# PicoMiteUSB.net
KiCad netlist of a schematic drawn in EasyEDA Pro
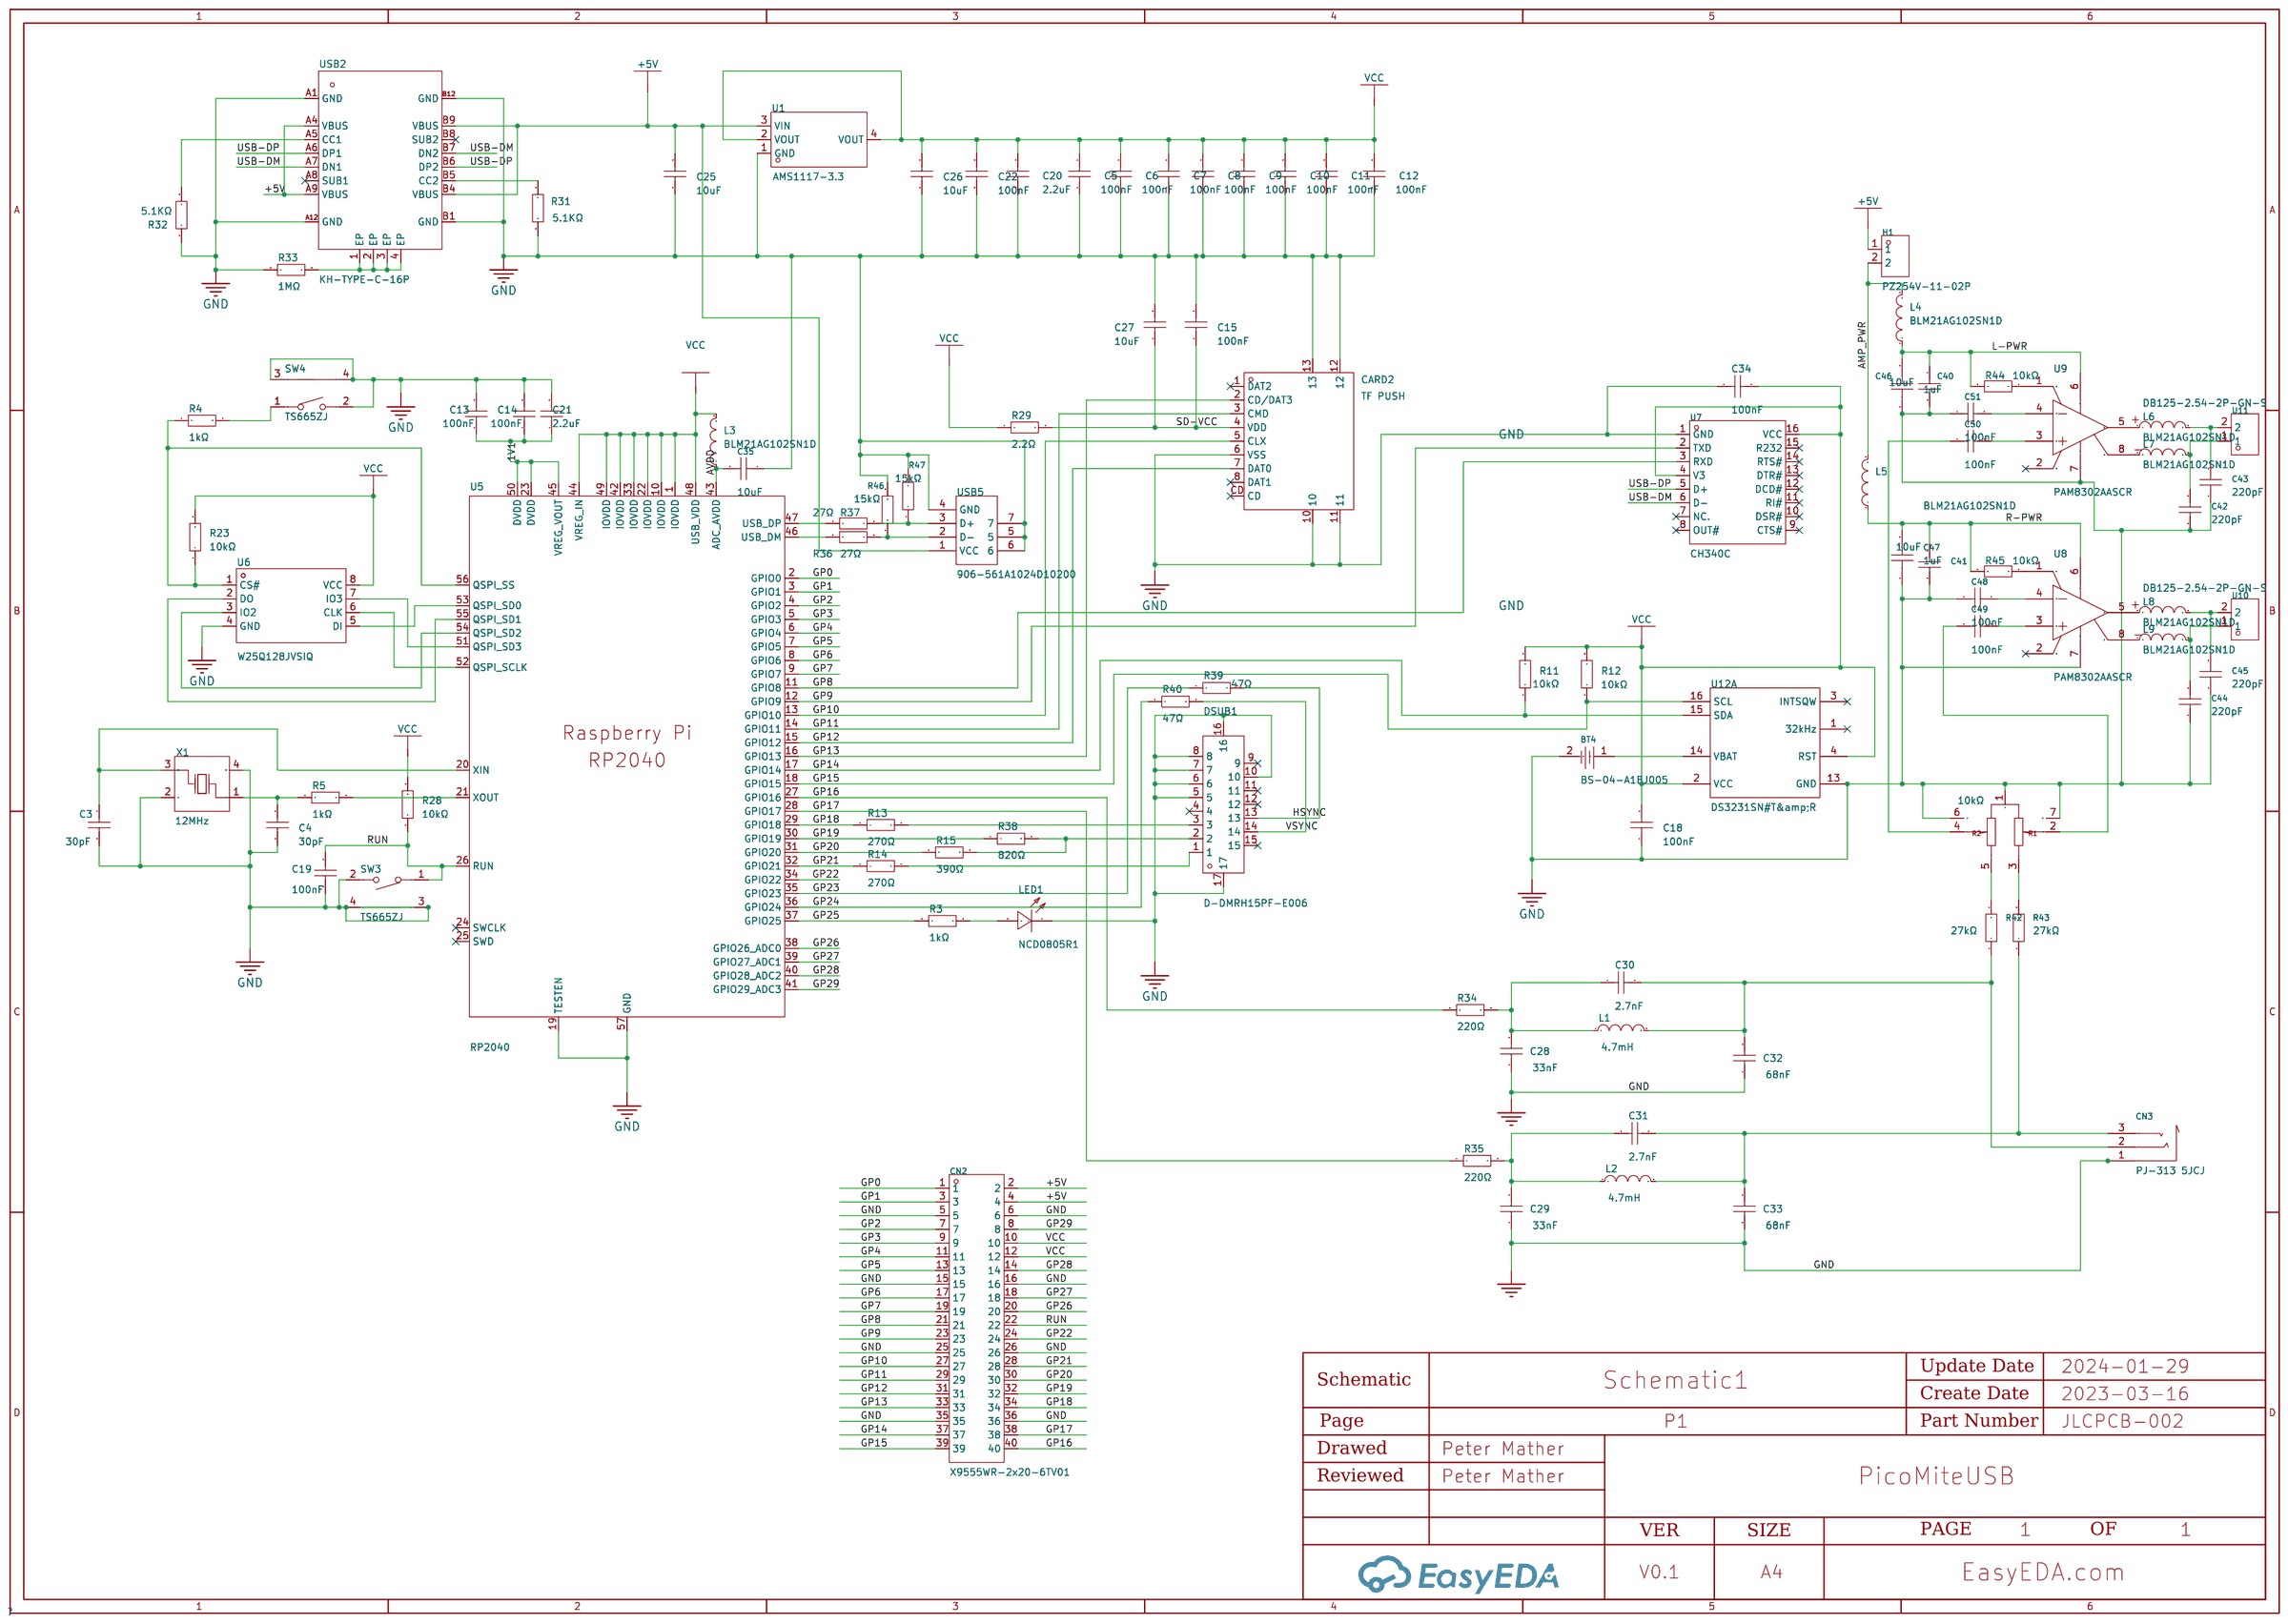
[diagram p0: schematic sheet]

(export (version "E")
  (design (tool "Eeschema 10.0.6"))
  (components
    (comp (ref "BT4")
      (value "BS-04-A1BJ005")
      (footprint "easyedapro:BAT-TH_BS-04-A1BJ004")
      (fields (field (name "Manufacturer") "MYOUNG(美阳)"))
      (libsource (lib "easyedapro") (part "BS-04-A1BJ005"))
    )
    (comp (ref "C3")
      (value "30pF")
      (footprint "easyedapro:C0805")
      (fields (field (name "Manufacturer Part") "0402CG300J500NT") (field (name "Manufacturer") "FH(风华)"))
      (libsource (lib "easyedapro") (part "CC0805JRNPO9BN300"))
    )
    (comp (ref "C4")
      (value "30pF")
      (footprint "easyedapro:C0805")
      (fields (field (name "Manufacturer Part") "0402CG300J500NT") (field (name "Manufacturer") "FH(风华)"))
      (libsource (lib "easyedapro") (part "CC0805JRNPO9BN300"))
    )
    (comp (ref "C5")
      (value "100nF")
      (footprint "easyedapro:C0603")
      (fields
        (field (name "Manufacturer Part") "CL05B104KO5NNNC")
        (field (name "Manufacturer") "SAMSUNG(三星)")
      )
      (libsource (lib "easyedapro") (part "CL10A225KO8NNNC"))
    )
    (comp (ref "C6")
      (value "100nF")
      (footprint "easyedapro:C0603")
      (fields
        (field (name "Manufacturer Part") "CL05B104KO5NNNC")
        (field (name "Manufacturer") "SAMSUNG(三星)")
      )
      (libsource (lib "easyedapro") (part "CL10A225KO8NNNC"))
    )
    (comp (ref "C7")
      (value "100nF")
      (footprint "easyedapro:C0603")
      (fields
        (field (name "Manufacturer Part") "CL05B104KO5NNNC")
        (field (name "Manufacturer") "SAMSUNG(三星)")
      )
      (libsource (lib "easyedapro") (part "CL10A225KO8NNNC"))
    )
    (comp (ref "C8")
      (value "100nF")
      (footprint "easyedapro:C0603")
      (fields
        (field (name "Manufacturer Part") "CL05B104KO5NNNC")
        (field (name "Manufacturer") "SAMSUNG(三星)")
      )
      (libsource (lib "easyedapro") (part "CL10A225KO8NNNC"))
    )
    (comp (ref "C9")
      (value "100nF")
      (footprint "easyedapro:C0603")
      (fields
        (field (name "Manufacturer Part") "CL05B104KO5NNNC")
        (field (name "Manufacturer") "SAMSUNG(三星)")
      )
      (libsource (lib "easyedapro") (part "CL10A225KO8NNNC"))
    )
    (comp (ref "C10")
      (value "100nF")
      (footprint "easyedapro:C0603")
      (fields
        (field (name "Manufacturer Part") "CL05B104KO5NNNC")
        (field (name "Manufacturer") "SAMSUNG(三星)")
      )
      (libsource (lib "easyedapro") (part "CL10A225KO8NNNC"))
    )
    (comp (ref "C11")
      (value "100nF")
      (footprint "easyedapro:C0603")
      (fields
        (field (name "Manufacturer Part") "CL05B104KO5NNNC")
        (field (name "Manufacturer") "SAMSUNG(三星)")
      )
      (libsource (lib "easyedapro") (part "CL10A225KO8NNNC"))
    )
    (comp (ref "C12")
      (value "100nF")
      (footprint "easyedapro:C0603")
      (fields
        (field (name "Manufacturer Part") "CL05B104KO5NNNC")
        (field (name "Manufacturer") "SAMSUNG(三星)")
      )
      (libsource (lib "easyedapro") (part "CL10A225KO8NNNC"))
    )
    (comp (ref "C13")
      (value "100nF")
      (footprint "easyedapro:C0603")
      (fields
        (field (name "Manufacturer Part") "CL05B104KO5NNNC")
        (field (name "Manufacturer") "SAMSUNG(三星)")
      )
      (libsource (lib "easyedapro") (part "CL10A225KO8NNNC"))
    )
    (comp (ref "C14")
      (value "100nF")
      (footprint "easyedapro:C0603")
      (fields
        (field (name "Manufacturer Part") "CL05B104KO5NNNC")
        (field (name "Manufacturer") "SAMSUNG(三星)")
      )
      (libsource (lib "easyedapro") (part "CL10A225KO8NNNC"))
    )
    (comp (ref "C15")
      (value "100nF")
      (footprint "easyedapro:C0603")
      (fields
        (field (name "Manufacturer Part") "CL05B104KO5NNNC")
        (field (name "Manufacturer") "SAMSUNG(三星)")
      )
      (libsource (lib "easyedapro") (part "CL10A225KO8NNNC"))
    )
    (comp (ref "C18")
      (value "100nF")
      (footprint "easyedapro:C0603")
      (fields
        (field (name "Manufacturer Part") "CL05B104KO5NNNC")
        (field (name "Manufacturer") "SAMSUNG(三星)")
      )
      (libsource (lib "easyedapro") (part "CL10A225KO8NNNC"))
    )
    (comp (ref "C19")
      (value "100nF")
      (footprint "easyedapro:C0603")
      (fields
        (field (name "Manufacturer Part") "CL05B104KO5NNNC")
        (field (name "Manufacturer") "SAMSUNG(三星)")
      )
      (libsource (lib "easyedapro") (part "CL10A225KO8NNNC"))
    )
    (comp (ref "C20")
      (value "2.2uF")
      (footprint "easyedapro:C0402_NEW")
      (fields
        (field (name "Manufacturer Part") "CL10A225KO8NNNC")
        (field (name "Manufacturer") "SAMSUNG(三星)")
      )
      (libsource (lib "easyedapro") (part "CL05B104KO5NNNC"))
    )
    (comp (ref "C21")
      (value "2.2uF")
      (footprint "easyedapro:C0402_NEW")
      (fields
        (field (name "Manufacturer Part") "CL10A225KO8NNNC")
        (field (name "Manufacturer") "SAMSUNG(三星)")
      )
      (libsource (lib "easyedapro") (part "CL05B104KO5NNNC"))
    )
    (comp (ref "C22")
      (value "100nF")
      (footprint "easyedapro:C0603")
      (fields
        (field (name "Manufacturer Part") "CL05B104KO5NNNC")
        (field (name "Manufacturer") "SAMSUNG(三星)")
      )
      (libsource (lib "easyedapro") (part "CL10A225KO8NNNC"))
    )
    (comp (ref "C25")
      (value "10uF")
      (footprint "easyedapro:C1206")
      (fields
        (field (name "Manufacturer Part") "CL31A106KBHNNNE")
        (field (name "Manufacturer") "SAMSUNG(三星)")
      )
      (libsource (lib "easyedapro") (part "CL31A106KBHNNNE"))
    )
    (comp (ref "C26")
      (value "10uF")
      (footprint "easyedapro:C1206")
      (fields
        (field (name "Manufacturer Part") "CL31A106KBHNNNE")
        (field (name "Manufacturer") "SAMSUNG(三星)")
      )
      (libsource (lib "easyedapro") (part "CL31A106KBHNNNE"))
    )
    (comp (ref "C27")
      (value "10uF")
      (footprint "easyedapro:C1206")
      (fields
        (field (name "Manufacturer Part") "CL31A106KBHNNNE")
        (field (name "Manufacturer") "SAMSUNG(三星)")
      )
      (libsource (lib "easyedapro") (part "CL31A106KBHNNNE"))
    )
    (comp (ref "C28")
      (value "33nF")
      (footprint "easyedapro:C0603")
      (fields
        (field (name "Manufacturer Part") "CL10B333KB8NNNC")
        (field (name "Manufacturer") "SAMSUNG(三星)")
      )
      (libsource (lib "easyedapro") (part "CL10B333KB8NNNC"))
    )
    (comp (ref "C29")
      (value "33nF")
      (footprint "easyedapro:C0603")
      (fields
        (field (name "Manufacturer Part") "CL10B333KB8NNNC")
        (field (name "Manufacturer") "SAMSUNG(三星)")
      )
      (libsource (lib "easyedapro") (part "CL10B333KB8NNNC"))
    )
    (comp (ref "C30")
      (value "2.7nF")
      (footprint "easyedapro:C0603")
      (fields (field (name "Manufacturer Part") "0603B272K500NT") (field (name "Manufacturer") "FH(风华)"))
      (libsource (lib "easyedapro") (part "0603B272K500NT"))
    )
    (comp (ref "C31")
      (value "2.7nF")
      (footprint "easyedapro:C0603")
      (fields (field (name "Manufacturer Part") "0603B272K500NT") (field (name "Manufacturer") "FH(风华)"))
      (libsource (lib "easyedapro") (part "0603B272K500NT"))
    )
    (comp (ref "C32")
      (value "68nF")
      (footprint "easyedapro:C0603")
      (fields
        (field (name "Manufacturer Part") "CL10B683KB8NNNC")
        (field (name "Manufacturer") "SAMSUNG(三星)")
      )
      (libsource (lib "easyedapro") (part "CL10B683KB8NNNC"))
    )
    (comp (ref "C33")
      (value "68nF")
      (footprint "easyedapro:C0603")
      (fields
        (field (name "Manufacturer Part") "CL10B683KB8NNNC")
        (field (name "Manufacturer") "SAMSUNG(三星)")
      )
      (libsource (lib "easyedapro") (part "CL10B683KB8NNNC"))
    )
    (comp (ref "C34")
      (value "100nF")
      (footprint "easyedapro:C0603")
      (fields
        (field (name "Manufacturer Part") "CL05B104KO5NNNC")
        (field (name "Manufacturer") "SAMSUNG(三星)")
      )
      (libsource (lib "easyedapro") (part "CL10A225KO8NNNC"))
    )
    (comp (ref "C35")
      (value "10uF")
      (footprint "easyedapro:C1206")
      (fields
        (field (name "Manufacturer Part") "CL31A106KBHNNNE")
        (field (name "Manufacturer") "SAMSUNG(三星)")
      )
      (libsource (lib "easyedapro") (part "CL31A106KBHNNNE"))
    )
    (comp (ref "C40")
      (value "10uF")
      (footprint "easyedapro:C1206")
      (fields
        (field (name "Manufacturer Part") "CL31A106KBHNNNE")
        (field (name "Manufacturer") "SAMSUNG(三星)")
      )
      (libsource (lib "easyedapro") (part "CL31A106KBHNNNE"))
    )
    (comp (ref "C41")
      (value "10uF")
      (footprint "easyedapro:C1206")
      (fields
        (field (name "Manufacturer Part") "CL31A106KBHNNNE")
        (field (name "Manufacturer") "SAMSUNG(三星)")
      )
      (libsource (lib "easyedapro") (part "CL31A106KBHNNNE"))
    )
    (comp (ref "C42")
      (value "220pF")
      (footprint "easyedapro:C0402")
      (fields (field (name "Manufacturer Part") "0402B221K500NT") (field (name "Manufacturer") "FH(风华)"))
      (libsource (lib "easyedapro") (part "0402B221K500NT"))
    )
    (comp (ref "C43")
      (value "220pF")
      (footprint "easyedapro:C0402")
      (fields (field (name "Manufacturer Part") "0402B221K500NT") (field (name "Manufacturer") "FH(风华)"))
      (libsource (lib "easyedapro") (part "0402B221K500NT"))
    )
    (comp (ref "C44")
      (value "220pF")
      (footprint "easyedapro:C0402")
      (fields (field (name "Manufacturer Part") "0402B221K500NT") (field (name "Manufacturer") "FH(风华)"))
      (libsource (lib "easyedapro") (part "0402B221K500NT"))
    )
    (comp (ref "C45")
      (value "220pF")
      (footprint "easyedapro:C0402")
      (fields (field (name "Manufacturer Part") "0402B221K500NT") (field (name "Manufacturer") "FH(风华)"))
      (libsource (lib "easyedapro") (part "0402B221K500NT"))
    )
    (comp (ref "C46")
      (value "1uF")
      (footprint "easyedapro:C1206")
      (fields
        (field (name "Manufacturer Part") "CL31B105KBHNNNE")
        (field (name "Manufacturer") "SAMSUNG(三星)")
      )
      (libsource (lib "easyedapro") (part "CL31B105KBHNNNE"))
    )
    (comp (ref "C47")
      (value "1uF")
      (footprint "easyedapro:C1206")
      (fields
        (field (name "Manufacturer Part") "CL31B105KBHNNNE")
        (field (name "Manufacturer") "SAMSUNG(三星)")
      )
      (libsource (lib "easyedapro") (part "CL31B105KBHNNNE"))
    )
    (comp (ref "C48")
      (value "100nF")
      (footprint "easyedapro:C0805")
      (fields
        (field (name "Manufacturer Part") "CC0805KRX7R9BB104")
        (field (name "Manufacturer") "YAGEO(国巨)")
      )
      (libsource (lib "easyedapro") (part "CC0805KRX7R9BB104"))
    )
    (comp (ref "C49")
      (value "100nF")
      (footprint "easyedapro:C0805")
      (fields
        (field (name "Manufacturer Part") "CC0805KRX7R9BB104")
        (field (name "Manufacturer") "YAGEO(国巨)")
      )
      (libsource (lib "easyedapro") (part "CC0805KRX7R9BB104"))
    )
    (comp (ref "C50")
      (value "100nF")
      (footprint "easyedapro:C0805")
      (fields
        (field (name "Manufacturer Part") "CC0805KRX7R9BB104")
        (field (name "Manufacturer") "YAGEO(国巨)")
      )
      (libsource (lib "easyedapro") (part "CC0805KRX7R9BB104"))
    )
    (comp (ref "C51")
      (value "100nF")
      (footprint "easyedapro:C0805")
      (fields
        (field (name "Manufacturer Part") "CC0805KRX7R9BB104")
        (field (name "Manufacturer") "YAGEO(国巨)")
      )
      (libsource (lib "easyedapro") (part "CC0805KRX7R9BB104"))
    )
    (comp (ref "CARD2")
      (value "TF PUSH")
      (footprint "easyedapro:TF-SMD_TF-PUSH")
      (fields (field (name "Manufacturer") "SHOU HAN(首韩)"))
      (libsource (lib "easyedapro") (part "TF PUSH"))
    )
    (comp (ref "CN2")
      (value "X9555WR-2x20-6TV01")
      (footprint "easyedapro:CONN-TH_X9555WR-2X20-6TV01")
      (fields (field (name "Manufacturer") "XKB Connectivity(中国星坤)"))
      (libsource (lib "easyedapro") (part "X9555WR-2X20-6TV01"))
    )
    (comp (ref "CN3")
      (value "PJ-313 5JCJ")
      (footprint "easyedapro:AUDIO-TH_PJ-313_5JCJ")
      (fields (field (name "Manufacturer") "SHOU HAN(首韩)"))
      (libsource (lib "easyedapro") (part "PJ-313 5JCJ"))
    )
    (comp (ref "DSUB1")
      (value "D-DMRH15PF-E006")
      (footprint "easyedapro:DSUB-TH_15P-P2.29-H-F_DDMRH15PFE006")
      (fields (field (name "Manufacturer") "Ckmtw(灿科盟)"))
      (libsource (lib "easyedapro") (part "DDMRH15PFE006"))
    )
    (comp (ref "H1")
      (value "PZ254V-11-02P")
      (footprint "easyedapro:HDR-TH_2P-P2.54-V-M")
      (fields (field (name "Manufacturer") "XFCN(兴飞)"))
      (libsource (lib "easyedapro") (part "PZ254V-11-02P"))
    )
    (comp (ref "L1")
      (value "4.7mH")
      (footprint "easyedapro:IND-SMD_L6.0-W6.0")
      (fields (field (name "Manufacturer Part") "YNR6045-472M") (field (name "Manufacturer") "YJYCOIN(益嘉源)"))
      (libsource (lib "easyedapro") (part "YNR6045-472M"))
    )
    (comp (ref "L2")
      (value "4.7mH")
      (footprint "easyedapro:IND-SMD_L6.0-W6.0")
      (fields (field (name "Manufacturer Part") "YNR6045-472M") (field (name "Manufacturer") "YJYCOIN(益嘉源)"))
      (libsource (lib "easyedapro") (part "YNR6045-472M"))
    )
    (comp (ref "L3")
      (value "BLM21AG102SN1D")
      (footprint "easyedapro:L0805")
      (fields (field (name "Manufacturer") "muRata(村田)"))
      (libsource (lib "easyedapro") (part "BLM21AG102SN1D"))
    )
    (comp (ref "L4")
      (value "BLM21AG102SN1D")
      (footprint "easyedapro:L0805")
      (fields (field (name "Manufacturer") "muRata(村田)"))
      (libsource (lib "easyedapro") (part "BLM21AG102SN1D"))
    )
    (comp (ref "L5")
      (value "BLM21AG102SN1D")
      (footprint "easyedapro:L0805")
      (fields (field (name "Manufacturer") "muRata(村田)"))
      (libsource (lib "easyedapro") (part "BLM21AG102SN1D"))
    )
    (comp (ref "L6")
      (value "BLM21AG102SN1D")
      (footprint "easyedapro:L0805")
      (fields (field (name "Manufacturer") "muRata(村田)"))
      (libsource (lib "easyedapro") (part "BLM21AG102SN1D"))
    )
    (comp (ref "L7")
      (value "BLM21AG102SN1D")
      (footprint "easyedapro:L0805")
      (fields (field (name "Manufacturer") "muRata(村田)"))
      (libsource (lib "easyedapro") (part "BLM21AG102SN1D"))
    )
    (comp (ref "L8")
      (value "BLM21AG102SN1D")
      (footprint "easyedapro:L0805")
      (fields (field (name "Manufacturer") "muRata(村田)"))
      (libsource (lib "easyedapro") (part "BLM21AG102SN1D"))
    )
    (comp (ref "L9")
      (value "BLM21AG102SN1D")
      (footprint "easyedapro:L0805")
      (fields (field (name "Manufacturer") "muRata(村田)"))
      (libsource (lib "easyedapro") (part "BLM21AG102SN1D"))
    )
    (comp (ref "LED1")
      (value "NCD0805R1")
      (footprint "easyedapro:LED0805-RD")
      (description "Emitted Color:红灯")
      (fields (field (name "Manufacturer") "国星光电"))
      (libsource (lib "easyedapro") (part "FC-2012HRK-620D"))
    )
    (comp (ref "R3")
      (value "1kΩ")
      (footprint "easyedapro:R0603")
      (fields
        (field (name "Manufacturer Part") "0603WAF1001T5E")
        (field (name "Manufacturer") "UNI-ROYAL(厚声)")
      )
      (libsource (lib "easyedapro") (part "0603WAF1001T5E"))
    )
    (comp (ref "R4")
      (value "1kΩ")
      (footprint "easyedapro:R0603")
      (fields
        (field (name "Manufacturer Part") "0603WAF1001T5E")
        (field (name "Manufacturer") "UNI-ROYAL(厚声)")
      )
      (libsource (lib "easyedapro") (part "0603WAF1001T5E"))
    )
    (comp (ref "R5")
      (value "1kΩ")
      (footprint "easyedapro:R0603")
      (fields
        (field (name "Manufacturer Part") "0603WAF1001T5E")
        (field (name "Manufacturer") "UNI-ROYAL(厚声)")
      )
      (libsource (lib "easyedapro") (part "0603WAF1001T5E"))
    )
    (comp (ref "R11")
      (value "10kΩ")
      (footprint "easyedapro:R0805")
      (fields
        (field (name "Manufacturer Part") "0805W8F1002T5E")
        (field (name "Manufacturer") "UNI-ROYAL(厚声)")
      )
      (libsource (lib "easyedapro") (part "0805W8F1002T5E"))
    )
    (comp (ref "R12")
      (value "10kΩ")
      (footprint "easyedapro:R0805")
      (fields
        (field (name "Manufacturer Part") "0805W8F1002T5E")
        (field (name "Manufacturer") "UNI-ROYAL(厚声)")
      )
      (libsource (lib "easyedapro") (part "0805W8F1002T5E"))
    )
    (comp (ref "R13")
      (value "270Ω")
      (footprint "easyedapro:R0603")
      (fields
        (field (name "Manufacturer Part") "0603WAF2700T5E")
        (field (name "Manufacturer") "UNI-ROYAL(厚声)")
      )
      (libsource (lib "easyedapro") (part "0603WAF2700T5E"))
    )
    (comp (ref "R14")
      (value "270Ω")
      (footprint "easyedapro:R0603")
      (fields
        (field (name "Manufacturer Part") "0603WAF2700T5E")
        (field (name "Manufacturer") "UNI-ROYAL(厚声)")
      )
      (libsource (lib "easyedapro") (part "0603WAF2700T5E"))
    )
    (comp (ref "R15")
      (value "390Ω")
      (footprint "easyedapro:R0603")
      (fields
        (field (name "Manufacturer Part") "0603WAF3900T5E")
        (field (name "Manufacturer") "UNI-ROYAL(厚声)")
      )
      (libsource (lib "easyedapro") (part "0603WAF3900T5E"))
    )
    (comp (ref "R23")
      (value "10kΩ")
      (footprint "easyedapro:R0402")
      (fields
        (field (name "Manufacturer Part") "0402WGF1002TCE")
        (field (name "Manufacturer") "UNI-ROYAL(厚声)")
      )
      (libsource (lib "easyedapro") (part "0402WGF1002TCE"))
    )
    (comp (ref "R28")
      (value "10kΩ")
      (footprint "easyedapro:R0402")
      (fields
        (field (name "Manufacturer Part") "0402WGF1002TCE")
        (field (name "Manufacturer") "UNI-ROYAL(厚声)")
      )
      (libsource (lib "easyedapro") (part "0402WGF1002TCE"))
    )
    (comp (ref "R29")
      (value "2.2Ω")
      (footprint "easyedapro:R0805")
      (fields (field (name "Manufacturer") "UNI-ROYAL(厚声)"))
      (libsource (lib "easyedapro") (part "0805W8F220KT5E"))
    )
    (comp (ref "R31")
      (value "5.1kΩ")
      (footprint "easyedapro:R0603")
      (fields
        (field (name "Manufacturer Part") "5.1KΩ")
        (field (name "Manufacturer") "UNI-ROYAL(厚声)")
        (field (name "Tolerance") "±1%")
      )
      (libsource (lib "easyedapro") (part "0603WAF5101T5E"))
    )
    (comp (ref "R32")
      (value "5.1kΩ")
      (footprint "easyedapro:R0603")
      (fields
        (field (name "Manufacturer Part") "5.1KΩ")
        (field (name "Manufacturer") "UNI-ROYAL(厚声)")
        (field (name "Tolerance") "±1%")
      )
      (libsource (lib "easyedapro") (part "0603WAF5101T5E"))
    )
    (comp (ref "R33")
      (value "1MΩ")
      (footprint "easyedapro:R0603")
      (fields
        (field (name "Manufacturer Part") "0402WGF1004TCE")
        (field (name "Manufacturer") "UNI-ROYAL(厚声)")
        (field (name "Tolerance") "±1%")
      )
      (libsource (lib "easyedapro") (part "0603WAF1004T5E"))
    )
    (comp (ref "R34")
      (value "220Ω")
      (footprint "easyedapro:R0603")
      (fields
        (field (name "Manufacturer Part") "0603WAF2200T5E")
        (field (name "Manufacturer") "UNI-ROYAL(厚声)")
      )
      (libsource (lib "easyedapro") (part "0603WAF2200T5E"))
    )
    (comp (ref "R35")
      (value "220Ω")
      (footprint "easyedapro:R0603")
      (fields
        (field (name "Manufacturer Part") "0603WAF2200T5E")
        (field (name "Manufacturer") "UNI-ROYAL(厚声)")
      )
      (libsource (lib "easyedapro") (part "0603WAF2200T5E"))
    )
    (comp (ref "R36")
      (value "27Ω")
      (footprint "easyedapro:R0603")
      (fields
        (field (name "Manufacturer Part") "0603WAF270JT5E")
        (field (name "Manufacturer") "UNI-ROYAL(厚声)")
      )
      (libsource (lib "easyedapro") (part "0603WAF270JT5E"))
    )
    (comp (ref "R37")
      (value "27Ω")
      (footprint "easyedapro:R0603")
      (fields
        (field (name "Manufacturer Part") "0603WAF270JT5E")
        (field (name "Manufacturer") "UNI-ROYAL(厚声)")
      )
      (libsource (lib "easyedapro") (part "0603WAF270JT5E"))
    )
    (comp (ref "R38")
      (value "820Ω")
      (footprint "easyedapro:R0603")
      (fields
        (field (name "Manufacturer Part") "0603WAF8200T5E")
        (field (name "Manufacturer") "UNI-ROYAL(厚声)")
      )
      (libsource (lib "easyedapro") (part "0603WAF8200T5E"))
    )
    (comp (ref "R39")
      (value "47Ω")
      (footprint "easyedapro:R0805")
      (fields
        (field (name "Manufacturer Part") "0805W8F470JT5E")
        (field (name "Manufacturer") "UNI-ROYAL(厚声)")
      )
      (libsource (lib "easyedapro") (part "0805W8F470JT5E"))
    )
    (comp (ref "R40")
      (value "47Ω")
      (footprint "easyedapro:R0805")
      (fields
        (field (name "Manufacturer Part") "0805W8F470JT5E")
        (field (name "Manufacturer") "UNI-ROYAL(厚声)")
      )
      (libsource (lib "easyedapro") (part "0805W8F470JT5E"))
    )
    (comp (ref "R42")
      (value "27kΩ")
      (footprint "easyedapro:R0805")
      (fields
        (field (name "Manufacturer Part") "0805W8F2702T5E")
        (field (name "Manufacturer") "UNI-ROYAL(厚声)")
      )
      (libsource (lib "easyedapro") (part "0805W8F2702T5E"))
    )
    (comp (ref "R43")
      (value "27kΩ")
      (footprint "easyedapro:R0805")
      (fields
        (field (name "Manufacturer Part") "0805W8F2702T5E")
        (field (name "Manufacturer") "UNI-ROYAL(厚声)")
      )
      (libsource (lib "easyedapro") (part "0805W8F2702T5E"))
    )
    (comp (ref "R44")
      (value "10kΩ")
      (footprint "easyedapro:R0805")
      (fields
        (field (name "Manufacturer Part") "0805W8F1002T5E")
        (field (name "Manufacturer") "UNI-ROYAL(厚声)")
      )
      (libsource (lib "easyedapro") (part "0805W8F1002T5E"))
    )
    (comp (ref "R45")
      (value "10kΩ")
      (footprint "easyedapro:R0805")
      (fields
        (field (name "Manufacturer Part") "0805W8F1002T5E")
        (field (name "Manufacturer") "UNI-ROYAL(厚声)")
      )
      (libsource (lib "easyedapro") (part "0805W8F1002T5E"))
    )
    (comp (ref "R46")
      (value "15kΩ")
      (footprint "easyedapro:R0805")
      (fields
        (field (name "Manufacturer Part") "0805W8F1502T5E")
        (field (name "Manufacturer") "UNI-ROYAL(厚声)")
      )
      (libsource (lib "easyedapro") (part "0805W8F1502T5E"))
    )
    (comp (ref "R47")
      (value "15kΩ")
      (footprint "easyedapro:R0805")
      (fields
        (field (name "Manufacturer Part") "0805W8F1502T5E")
        (field (name "Manufacturer") "UNI-ROYAL(厚声)")
      )
      (libsource (lib "easyedapro") (part "0805W8F1502T5E"))
    )
    (comp (ref "SW3")
      (value "TS665ZJ")
      (footprint "easyedapro:SW-TH_TS665ZJ")
      (fields (field (name "Manufacturer") "SHOU HAN(首韩)"))
      (libsource (lib "easyedapro") (part "TS665ZJ"))
    )
    (comp (ref "SW4")
      (value "TS665ZJ")
      (footprint "easyedapro:SW-TH_TS665ZJ")
      (fields (field (name "Manufacturer") "SHOU HAN(首韩)"))
      (libsource (lib "easyedapro") (part "TS665ZJ"))
    )
    (comp (ref "U1")
      (value "AMS1117-3.3")
      (footprint "easyedapro:SOT-223-3_L6.5-W3.4-P2.30-LS7.0-BR")
      (fields (field (name "Manufacturer") "AMS"))
      (libsource (lib "easyedapro") (part "AMS1117-3.3"))
    )
    (comp (ref "U5")
      (value "RP2040")
      (footprint "easyedapro:LQFN-56_L7.0-W7.0-P0.4-EP")
      (fields (field (name "Manufacturer") "Raspberry Pi(树莓派)"))
      (libsource (lib "easyedapro") (part "RP2040"))
    )
    (comp (ref "U6")
      (value "W25Q128JVSIQ")
      (footprint "easyedapro:SOIC-8_L5.3-W5.3-P1.27-LS8.0-BL")
      (fields (field (name "Manufacturer") "WINBOND(华邦)"))
      (libsource (lib "easyedapro") (part "W25Q128JVSIQTR"))
    )
    (comp (ref "U7")
      (value "CH340C")
      (footprint "easyedapro:SOP-16_L10.0-W3.9-P1.27-LS6.0-BL")
      (fields (field (name "Manufacturer") "WCH(南京沁恒)"))
      (libsource (lib "easyedapro") (part "CH340C"))
    )
    (comp (ref "U8")
      (value "PAM8302AASCR")
      (footprint "easyedapro:MSOP-8_L3.0-W3.0-P0.65-LS5.0-BL")
      (fields (field (name "Manufacturer") "DIODES(美台)"))
      (libsource (lib "easyedapro") (part "PAM8302AASCR"))
    )
    (comp (ref "U9")
      (value "PAM8302AASCR")
      (footprint "easyedapro:MSOP-8_L3.0-W3.0-P0.65-LS5.0-BL")
      (fields (field (name "Manufacturer") "DIODES(美台)"))
      (libsource (lib "easyedapro") (part "PAM8302AASCR"))
    )
    (comp (ref "U10")
      (value "DB125-2.54-2P-GN-S")
      (footprint "easyedapro:CONN-TH_DB125-2.54-2P-GN")
      (fields (field (name "Manufacturer") "DIBO(地博电气)"))
      (libsource (lib "easyedapro") (part "DB125-2.54-2P-GN"))
    )
    (comp (ref "U11")
      (value "DB125-2.54-2P-GN-S")
      (footprint "easyedapro:CONN-TH_DB125-2.54-2P-GN")
      (fields (field (name "Manufacturer") "DIBO(地博电气)"))
      (libsource (lib "easyedapro") (part "DB125-2.54-2P-GN"))
    )
    (comp (ref "U12")
      (value "DS3231SN#T&amp;R")
      (footprint "easyedapro:SOIC-16_L10.3-W7.5-P1.27-LS10.3-BL")
      (description "Interface:I2C Operating Voltage:2.3V~5.5V Operating Voltage:2.3V~5.5V")
      (fields (field (name "Manufacturer") "ADI(亚德诺)/MAXIM(美信)"))
      (libsource (lib "easyedapro") (part "DS3231SN#"))
    )
    (comp (ref "USB2")
      (value "KH-TYPE-C-16P")
      (footprint "easyedapro:USB-C-SMD_KH-TYPE-C-16P")
      (fields (field (name "Manufacturer") "kinghelm(金航标)"))
      (libsource (lib "easyedapro") (part "KH-TYPE-C-16P"))
    )
    (comp (ref "USB5")
      (value "906-561A1024D10200")
      (footprint "easyedapro:USB-A-TH_C39450")
      (fields (field (name "Manufacturer") "精拓金"))
      (libsource (lib "easyedapro") (part "USB-AF-13.1X10.4-H5.1"))
    )
    (comp (ref "VR1")
      (value "10kΩ")
      (footprint "easyedapro:RES-TH_RK10J12E002L")
      (description "Resistance: Tolerance:±30% Tolerance:±30%")
      (fields
        (field (name "Manufacturer Part") "RK10J12E002L")
        (field (name "Manufacturer") "ALPSALPINE(阿尔卑斯阿尔派)")
      )
      (libsource (lib "easyedapro") (part "RK10J12E002L"))
    )
    (comp (ref "X1")
      (value "12MHz")
      (footprint "easyedapro:OSC-SMD_4P-L3.2-W2.5-BL")
      (fields (field (name "Manufacturer Part") "X322512MSB4SI") (field (name "Manufacturer") "YXC(扬兴晶振)"))
      (libsource (lib "easyedapro") (part "X322512MSB4SI"))
    )
  )
  (nets
    (net (code "1") (name "+5V") (class "Default")
      (node (ref "C25") (pin "2") (pinfunction "2_2") (pintype "input"))
      (node (ref "CN2") (pin "2") (pinfunction "2_2") (pintype "input"))
      (node (ref "CN2") (pin "4") (pinfunction "4_4") (pintype "input"))
      (node (ref "H1") (pin "1") (pinfunction "1_1") (pintype "input"))
      (node (ref "U1") (pin "3") (pinfunction "VIN_3") (pintype "input"))
      (node (ref "USB2") (pin "A4") (pinfunction "VBUS_A4") (pintype "input"))
      (node (ref "USB2") (pin "A9") (pinfunction "VBUS_A9") (pintype "input"))
      (node (ref "USB2") (pin "B4") (pinfunction "VBUS_B4") (pintype "input"))
      (node (ref "USB2") (pin "B9") (pinfunction "VBUS_B9") (pintype "input"))
      (node (ref "USB5") (pin "1") (pinfunction "VCC_1") (pintype "unspecified"))
    )
    (net (code "2") (name "/1V1") (class "Default")
      (node (ref "C13") (pin "1") (pinfunction "1_1") (pintype "input"))
      (node (ref "C14") (pin "1") (pinfunction "1_1") (pintype "input"))
      (node (ref "C21") (pin "1") (pinfunction "1_1") (pintype "input"))
      (node (ref "U5") (pin "23") (pinfunction "DVDD_23") (pintype "bidirectional"))
      (node (ref "U5") (pin "45") (pinfunction "VREG_VOUT_45") (pintype "bidirectional"))
      (node (ref "U5") (pin "50") (pinfunction "DVDD_50") (pintype "bidirectional"))
    )
    (net (code "3") (name "/AMP_PWR") (class "Default")
      (node (ref "H1") (pin "2") (pinfunction "2_2") (pintype "input"))
      (node (ref "L4") (pin "2") (pinfunction "2_2") (pintype "input"))
      (node (ref "L5") (pin "2") (pinfunction "2_2") (pintype "input"))
    )
    (net (code "4") (name "/AVDD") (class "Default")
      (node (ref "C35") (pin "2") (pinfunction "2_2") (pintype "input"))
      (node (ref "L3") (pin "1") (pinfunction "1_1") (pintype "input"))
      (node (ref "U5") (pin "43") (pinfunction "ADC_AVDD_43") (pintype "bidirectional"))
    )
    (net (code "5") (name "/GP0") (class "Default")
      (node (ref "CN2") (pin "1") (pinfunction "1_1") (pintype "input"))
      (node (ref "U5") (pin "2") (pinfunction "GPIO0_2") (pintype "bidirectional"))
    )
    (net (code "6") (name "/GP1") (class "Default")
      (node (ref "CN2") (pin "3") (pinfunction "3_3") (pintype "input"))
      (node (ref "U5") (pin "3") (pinfunction "GPIO1_3") (pintype "bidirectional"))
    )
    (net (code "7") (name "/GP2") (class "Default")
      (node (ref "CN2") (pin "7") (pinfunction "7_7") (pintype "input"))
      (node (ref "U5") (pin "4") (pinfunction "GPIO2_4") (pintype "bidirectional"))
    )
    (net (code "8") (name "/GP3") (class "Default")
      (node (ref "CN2") (pin "9") (pinfunction "9_9") (pintype "input"))
      (node (ref "U5") (pin "5") (pinfunction "GPIO3_5") (pintype "bidirectional"))
    )
    (net (code "9") (name "/GP4") (class "Default")
      (node (ref "CN2") (pin "11") (pinfunction "11_11") (pintype "input"))
      (node (ref "U5") (pin "6") (pinfunction "GPIO4_6") (pintype "bidirectional"))
    )
    (net (code "10") (name "/GP5") (class "Default")
      (node (ref "CN2") (pin "13") (pinfunction "13_13") (pintype "input"))
      (node (ref "U5") (pin "7") (pinfunction "GPIO5_7") (pintype "bidirectional"))
    )
    (net (code "11") (name "/GP6") (class "Default")
      (node (ref "CN2") (pin "17") (pinfunction "17_17") (pintype "input"))
      (node (ref "U5") (pin "8") (pinfunction "GPIO6_8") (pintype "bidirectional"))
    )
    (net (code "12") (name "/GP7") (class "Default")
      (node (ref "CN2") (pin "19") (pinfunction "19_19") (pintype "input"))
      (node (ref "U5") (pin "9") (pinfunction "GPIO7_9") (pintype "bidirectional"))
    )
    (net (code "13") (name "/GP8") (class "Default")
      (node (ref "CN2") (pin "21") (pinfunction "21_21") (pintype "input"))
      (node (ref "U5") (pin "11") (pinfunction "GPIO8_11") (pintype "bidirectional"))
      (node (ref "U7") (pin "3") (pinfunction "RXD_3") (pintype "input"))
    )
    (net (code "14") (name "/GP9") (class "Default")
      (node (ref "CN2") (pin "23") (pinfunction "23_23") (pintype "input"))
      (node (ref "U5") (pin "12") (pinfunction "GPIO9_12") (pintype "bidirectional"))
      (node (ref "U7") (pin "2") (pinfunction "TXD_2") (pintype "input"))
    )
    (net (code "15") (name "/GP10") (class "Default")
      (node (ref "CARD2") (pin "5") (pinfunction "CLX_5") (pintype "input"))
      (node (ref "CN2") (pin "27") (pinfunction "27_27") (pintype "input"))
      (node (ref "U5") (pin "13") (pinfunction "GPIO10_13") (pintype "bidirectional"))
    )
    (net (code "16") (name "/GP11") (class "Default")
      (node (ref "CARD2") (pin "3") (pinfunction "CMD_3") (pintype "input"))
      (node (ref "CN2") (pin "29") (pinfunction "29_29") (pintype "input"))
      (node (ref "U5") (pin "14") (pinfunction "GPIO11_14") (pintype "bidirectional"))
    )
    (net (code "17") (name "/GP12") (class "Default")
      (node (ref "CARD2") (pin "7") (pinfunction "DAT0_7") (pintype "input"))
      (node (ref "CN2") (pin "31") (pinfunction "31_31") (pintype "input"))
      (node (ref "U5") (pin "15") (pinfunction "GPIO12_15") (pintype "bidirectional"))
    )
    (net (code "18") (name "/GP13") (class "Default")
      (node (ref "CARD2") (pin "2") (pinfunction "CD/DAT3_2") (pintype "input"))
      (node (ref "CN2") (pin "33") (pinfunction "33_33") (pintype "input"))
      (node (ref "U5") (pin "16") (pinfunction "GPIO13_16") (pintype "bidirectional"))
    )
    (net (code "19") (name "/GP14") (class "Default")
      (node (ref "CN2") (pin "37") (pinfunction "37_37") (pintype "input"))
      (node (ref "R11") (pin "1") (pinfunction "1_1") (pintype "input"))
      (node (ref "U12") (pin "15") (pinfunction "SDA_15") (pintype "bidirectional"))
      (node (ref "U5") (pin "17") (pinfunction "GPIO14_17") (pintype "bidirectional"))
    )
    (net (code "20") (name "/GP15") (class "Default")
      (node (ref "CN2") (pin "39") (pinfunction "39_39") (pintype "input"))
      (node (ref "R12") (pin "1") (pinfunction "1_1") (pintype "input"))
      (node (ref "U12") (pin "16") (pinfunction "SCL_16") (pintype "unspecified"))
      (node (ref "U5") (pin "18") (pinfunction "GPIO15_18") (pintype "bidirectional"))
    )
    (net (code "21") (name "/GP16") (class "Default")
      (node (ref "CN2") (pin "40") (pinfunction "40_40") (pintype "input"))
      (node (ref "R34") (pin "1") (pinfunction "1_1") (pintype "input"))
      (node (ref "U5") (pin "27") (pinfunction "GPIO16_27") (pintype "bidirectional"))
    )
    (net (code "22") (name "/GP17") (class "Default")
      (node (ref "CN2") (pin "38") (pinfunction "38_38") (pintype "input"))
      (node (ref "R35") (pin "1") (pinfunction "1_1") (pintype "input"))
      (node (ref "U5") (pin "28") (pinfunction "GPIO17_28") (pintype "bidirectional"))
    )
    (net (code "23") (name "/GP18") (class "Default")
      (node (ref "CN2") (pin "34") (pinfunction "34_34") (pintype "input"))
      (node (ref "R13") (pin "1") (pinfunction "1_1") (pintype "input"))
      (node (ref "U5") (pin "29") (pinfunction "GPIO18_29") (pintype "bidirectional"))
    )
    (net (code "24") (name "/GP19") (class "Default")
      (node (ref "CN2") (pin "32") (pinfunction "32_32") (pintype "input"))
      (node (ref "R38") (pin "1") (pinfunction "1_1") (pintype "input"))
      (node (ref "U5") (pin "30") (pinfunction "GPIO19_30") (pintype "bidirectional"))
    )
    (net (code "25") (name "/GP20") (class "Default")
      (node (ref "CN2") (pin "30") (pinfunction "30_30") (pintype "input"))
      (node (ref "R15") (pin "1") (pinfunction "1_1") (pintype "input"))
      (node (ref "U5") (pin "31") (pinfunction "GPIO20_31") (pintype "bidirectional"))
    )
    (net (code "26") (name "/GP21") (class "Default")
      (node (ref "CN2") (pin "28") (pinfunction "28_28") (pintype "input"))
      (node (ref "R14") (pin "1") (pinfunction "1_1") (pintype "input"))
      (node (ref "U5") (pin "32") (pinfunction "GPIO21_32") (pintype "bidirectional"))
    )
    (net (code "27") (name "/GP22") (class "Default")
      (node (ref "CN2") (pin "24") (pinfunction "24_24") (pintype "input"))
      (node (ref "U5") (pin "34") (pinfunction "GPIO22_34") (pintype "bidirectional"))
    )
    (net (code "28") (name "/GP23") (class "Default")
      (node (ref "R39") (pin "1") (pinfunction "1_1") (pintype "input"))
      (node (ref "U5") (pin "35") (pinfunction "GPIO23_35") (pintype "bidirectional"))
    )
    (net (code "29") (name "/GP24") (class "Default")
      (node (ref "R40") (pin "1") (pinfunction "1_1") (pintype "input"))
      (node (ref "U5") (pin "36") (pinfunction "GPIO24_36") (pintype "bidirectional"))
    )
    (net (code "30") (name "/GP25") (class "Default")
      (node (ref "R3") (pin "1") (pinfunction "1_1") (pintype "input"))
      (node (ref "U5") (pin "37") (pinfunction "GPIO25_37") (pintype "bidirectional"))
    )
    (net (code "31") (name "/GP26") (class "Default")
      (node (ref "CN2") (pin "20") (pinfunction "20_20") (pintype "input"))
      (node (ref "U5") (pin "38") (pinfunction "GPIO26_ADC0_38") (pintype "bidirectional"))
    )
    (net (code "32") (name "/GP27") (class "Default")
      (node (ref "CN2") (pin "18") (pinfunction "18_18") (pintype "input"))
      (node (ref "U5") (pin "39") (pinfunction "GPIO27_ADC1_39") (pintype "bidirectional"))
    )
    (net (code "33") (name "/GP28") (class "Default")
      (node (ref "CN2") (pin "14") (pinfunction "14_14") (pintype "input"))
      (node (ref "U5") (pin "40") (pinfunction "GPIO28_ADC2_40") (pintype "bidirectional"))
    )
    (net (code "34") (name "/GP29") (class "Default")
      (node (ref "CN2") (pin "8") (pinfunction "8_8") (pintype "input"))
      (node (ref "U5") (pin "41") (pinfunction "GPIO29_ADC3_41") (pintype "bidirectional"))
    )
    (net (code "35") (name "/HSYNC") (class "Default")
      (node (ref "DSUB1") (pin "13") (pinfunction "13_13") (pintype "input"))
      (node (ref "R39") (pin "2") (pinfunction "2_2") (pintype "input"))
    )
    (net (code "36") (name "/L-PWR") (class "Default")
      (node (ref "C40") (pin "1") (pinfunction "1_1") (pintype "input"))
      (node (ref "C46") (pin "2") (pinfunction "2_2") (pintype "input"))
      (node (ref "L4") (pin "1") (pinfunction "1_1") (pintype "input"))
      (node (ref "R44") (pin "2") (pinfunction "2_2") (pintype "input"))
      (node (ref "U9") (pin "6") (pinfunction "VDD_6") (pintype "input"))
    )
    (net (code "37") (name "/R-PWR") (class "Default")
      (node (ref "C41") (pin "1") (pinfunction "1_1") (pintype "input"))
      (node (ref "C47") (pin "2") (pinfunction "2_2") (pintype "input"))
      (node (ref "L5") (pin "1") (pinfunction "1_1") (pintype "input"))
      (node (ref "R45") (pin "2") (pinfunction "2_2") (pintype "input"))
      (node (ref "U8") (pin "6") (pinfunction "VDD_6") (pintype "input"))
    )
    (net (code "38") (name "/RUN") (class "Default")
      (node (ref "C19") (pin "2") (pinfunction "2_2") (pintype "input"))
      (node (ref "CN2") (pin "22") (pinfunction "22_22") (pintype "input"))
      (node (ref "R28") (pin "1") (pinfunction "1_1") (pintype "input"))
      (node (ref "SW3") (pin "1") (pinfunction "1_1") (pintype "input"))
      (node (ref "U5") (pin "26") (pinfunction "RUN_26") (pintype "input"))
    )
    (net (code "39") (name "/SD-VCC") (class "Default")
      (node (ref "C15") (pin "1") (pinfunction "1_1") (pintype "input"))
      (node (ref "C27") (pin "1") (pinfunction "1_1") (pintype "input"))
      (node (ref "CARD2") (pin "4") (pinfunction "VDD_4") (pintype "input"))
      (node (ref "R29") (pin "2") (pinfunction "2_2") (pintype "input"))
    )
    (net (code "40") (name "/USB-DM") (class "Default")
      (node (ref "U7") (pin "6") (pinfunction "D-_6") (pintype "input"))
      (node (ref "USB2") (pin "A7") (pinfunction "DN1_A7") (pintype "input"))
      (node (ref "USB2") (pin "B7") (pinfunction "DN2_B7") (pintype "input"))
    )
    (net (code "41") (name "/USB-DP") (class "Default")
      (node (ref "U7") (pin "5") (pinfunction "D+_5") (pintype "input"))
      (node (ref "USB2") (pin "A6") (pinfunction "DP1_A6") (pintype "input"))
      (node (ref "USB2") (pin "B6") (pinfunction "DP2_B6") (pintype "input"))
    )
    (net (code "42") (name "/VSYNC") (class "Default")
      (node (ref "DSUB1") (pin "14") (pinfunction "14_14") (pintype "input"))
      (node (ref "R40") (pin "2") (pinfunction "2_2") (pintype "input"))
    )
    (net (code "43") (name "GND") (class "Default")
      (node (ref "BT4") (pin "2") (pinfunction "2_2") (pintype "input"))
      (node (ref "C10") (pin "1") (pinfunction "1_1") (pintype "input"))
      (node (ref "C11") (pin "1") (pinfunction "1_1") (pintype "input"))
      (node (ref "C12") (pin "1") (pinfunction "1_1") (pintype "input"))
      (node (ref "C13") (pin "2") (pinfunction "2_2") (pintype "input"))
      (node (ref "C14") (pin "2") (pinfunction "2_2") (pintype "input"))
      (node (ref "C15") (pin "2") (pinfunction "2_2") (pintype "input"))
      (node (ref "C18") (pin "1") (pinfunction "1_1") (pintype "input"))
      (node (ref "C19") (pin "1") (pinfunction "1_1") (pintype "input"))
      (node (ref "C20") (pin "1") (pinfunction "1_1") (pintype "input"))
      (node (ref "C21") (pin "2") (pinfunction "2_2") (pintype "input"))
      (node (ref "C22") (pin "1") (pinfunction "1_1") (pintype "input"))
      (node (ref "C25") (pin "1") (pinfunction "1_1") (pintype "input"))
      (node (ref "C26") (pin "1") (pinfunction "1_1") (pintype "input"))
      (node (ref "C27") (pin "2") (pinfunction "2_2") (pintype "input"))
      (node (ref "C28") (pin "1") (pinfunction "1_1") (pintype "input"))
      (node (ref "C29") (pin "1") (pinfunction "1_1") (pintype "input"))
      (node (ref "C3") (pin "1") (pinfunction "1_1") (pintype "input"))
      (node (ref "C32") (pin "1") (pinfunction "1_1") (pintype "input"))
      (node (ref "C33") (pin "1") (pinfunction "1_1") (pintype "input"))
      (node (ref "C34") (pin "2") (pinfunction "2_2") (pintype "input"))
      (node (ref "C35") (pin "1") (pinfunction "1_1") (pintype "input"))
      (node (ref "C4") (pin "1") (pinfunction "1_1") (pintype "input"))
      (node (ref "C40") (pin "2") (pinfunction "2_2") (pintype "input"))
      (node (ref "C41") (pin "2") (pinfunction "2_2") (pintype "input"))
      (node (ref "C42") (pin "1") (pinfunction "1_1") (pintype "input"))
      (node (ref "C43") (pin "1") (pinfunction "1_1") (pintype "input"))
      (node (ref "C44") (pin "1") (pinfunction "1_1") (pintype "input"))
      (node (ref "C45") (pin "1") (pinfunction "1_1") (pintype "input"))
      (node (ref "C46") (pin "1") (pinfunction "1_1") (pintype "input"))
      (node (ref "C47") (pin "1") (pinfunction "1_1") (pintype "input"))
      (node (ref "C48") (pin "1") (pinfunction "1_1") (pintype "input"))
      (node (ref "C5") (pin "1") (pinfunction "1_1") (pintype "input"))
      (node (ref "C51") (pin "1") (pinfunction "1_1") (pintype "input"))
      (node (ref "C6") (pin "1") (pinfunction "1_1") (pintype "input"))
      (node (ref "C7") (pin "1") (pinfunction "1_1") (pintype "input"))
      (node (ref "C8") (pin "1") (pinfunction "1_1") (pintype "input"))
      (node (ref "C9") (pin "1") (pinfunction "1_1") (pintype "input"))
      (node (ref "CARD2") (pin "10") (pinfunction "10_10") (pintype "input"))
      (node (ref "CARD2") (pin "11") (pinfunction "11_11") (pintype "input"))
      (node (ref "CARD2") (pin "12") (pinfunction "12_12") (pintype "input"))
      (node (ref "CARD2") (pin "13") (pinfunction "13_13") (pintype "input"))
      (node (ref "CARD2") (pin "6") (pinfunction "VSS_6") (pintype "input"))
      (node (ref "CN2") (pin "15") (pinfunction "15_15") (pintype "input"))
      (node (ref "CN2") (pin "16") (pinfunction "16_16") (pintype "input"))
      (node (ref "CN2") (pin "25") (pinfunction "25_25") (pintype "input"))
      (node (ref "CN2") (pin "26") (pinfunction "26_26") (pintype "input"))
      (node (ref "CN2") (pin "35") (pinfunction "35_35") (pintype "input"))
      (node (ref "CN2") (pin "36") (pinfunction "36_36") (pintype "input"))
      (node (ref "CN2") (pin "5") (pinfunction "5_5") (pintype "input"))
      (node (ref "CN2") (pin "6") (pinfunction "6_6") (pintype "input"))
      (node (ref "CN3") (pin "1") (pinfunction "1_1") (pintype "input"))
      (node (ref "DSUB1") (pin "10") (pinfunction "10_10") (pintype "input"))
      (node (ref "DSUB1") (pin "16") (pinfunction "16_16") (pintype "input"))
      (node (ref "DSUB1") (pin "17") (pinfunction "17_17") (pintype "input"))
      (node (ref "DSUB1") (pin "5") (pinfunction "5_5") (pintype "input"))
      (node (ref "DSUB1") (pin "6") (pinfunction "6_6") (pintype "input"))
      (node (ref "DSUB1") (pin "7") (pinfunction "7_7") (pintype "input"))
      (node (ref "DSUB1") (pin "8") (pinfunction "8_8") (pintype "input"))
      (node (ref "LED1") (pin "1") (pinfunction "-_1") (pintype "input"))
      (node (ref "R31") (pin "1") (pinfunction "1_1") (pintype "input"))
      (node (ref "R32") (pin "1") (pinfunction "1_1") (pintype "input"))
      (node (ref "R33") (pin "1") (pinfunction "1_1") (pintype "input"))
      (node (ref "R46") (pin "2") (pinfunction "2_2") (pintype "input"))
      (node (ref "R47") (pin "2") (pinfunction "2_2") (pintype "input"))
      (node (ref "SW3") (pin "2") (pinfunction "2_2") (pintype "input"))
      (node (ref "SW3") (pin "3") (pinfunction "3_3") (pintype "input"))
      (node (ref "SW3") (pin "4") (pinfunction "4_4") (pintype "input"))
      (node (ref "SW4") (pin "2") (pinfunction "2_2") (pintype "input"))
      (node (ref "SW4") (pin "3") (pinfunction "3_3") (pintype "input"))
      (node (ref "SW4") (pin "4") (pinfunction "4_4") (pintype "input"))
      (node (ref "U1") (pin "1") (pinfunction "GND_1") (pintype "input"))
      (node (ref "U12") (pin "13") (pinfunction "GND_13") (pintype "unspecified"))
      (node (ref "U5") (pin "19") (pinfunction "TESTEN_19") (pintype "input"))
      (node (ref "U5") (pin "57") (pinfunction "GND_57") (pintype "bidirectional"))
      (node (ref "U6") (pin "4") (pinfunction "GND_4") (pintype "input"))
      (node (ref "U7") (pin "1") (pinfunction "GND_1") (pintype "input"))
      (node (ref "U8") (pin "7") (pinfunction "GND_7") (pintype "input"))
      (node (ref "U9") (pin "7") (pinfunction "GND_7") (pintype "input"))
      (node (ref "USB2") (pin "A1") (pinfunction "GND_A1") (pintype "input"))
      (node (ref "USB2") (pin "A12") (pinfunction "GND_A12") (pintype "input"))
      (node (ref "USB2") (pin "B1") (pinfunction "GND_B1") (pintype "input"))
      (node (ref "USB2") (pin "B12") (pinfunction "GND_B12") (pintype "input"))
      (node (ref "USB5") (pin "4") (pinfunction "GND_4") (pintype "unspecified"))
      (node (ref "USB5") (pin "5") (pinfunction "5_5") (pintype "unspecified"))
      (node (ref "USB5") (pin "6") (pinfunction "6_6") (pintype "unspecified"))
      (node (ref "USB5") (pin "7") (pinfunction "7_7") (pintype "unspecified"))
      (node (ref "VR1") (pin "1") (pinfunction "1_1") (pintype "input"))
      (node (ref "VR1") (pin "6") (pinfunction "EH_6") (pintype "input"))
      (node (ref "VR1") (pin "7") (pinfunction "EH_7") (pintype "input"))
      (node (ref "X1") (pin "2") (pinfunction "GND_2") (pintype "input"))
      (node (ref "X1") (pin "4") (pinfunction "GND_4") (pintype "input"))
    )
    (net (code "44") (name "Net-(C28-Pad2)") (class "Default")
      (node (ref "C28") (pin "2") (pinfunction "2_2") (pintype "input"))
      (node (ref "C30") (pin "1") (pinfunction "1_1") (pintype "input"))
      (node (ref "L1") (pin "1") (pinfunction "1_1") (pintype "input"))
      (node (ref "R34") (pin "2") (pinfunction "2_2") (pintype "input"))
    )
    (net (code "45") (name "Net-(C29-Pad2)") (class "Default")
      (node (ref "C29") (pin "2") (pinfunction "2_2") (pintype "input"))
      (node (ref "C31") (pin "1") (pinfunction "1_1") (pintype "input"))
      (node (ref "L2") (pin "1") (pinfunction "1_1") (pintype "input"))
      (node (ref "R35") (pin "2") (pinfunction "2_2") (pintype "input"))
    )
    (net (code "46") (name "Net-(C30-Pad2)") (class "Default")
      (node (ref "C30") (pin "2") (pinfunction "2_2") (pintype "input"))
      (node (ref "C32") (pin "2") (pinfunction "2_2") (pintype "input"))
      (node (ref "CN3") (pin "2") (pinfunction "2_2") (pintype "input"))
      (node (ref "L1") (pin "2") (pinfunction "2_2") (pintype "input"))
      (node (ref "R42") (pin "1") (pinfunction "1_1") (pintype "input"))
    )
    (net (code "47") (name "Net-(C31-Pad2)") (class "Default")
      (node (ref "C31") (pin "2") (pinfunction "2_2") (pintype "input"))
      (node (ref "C33") (pin "2") (pinfunction "2_2") (pintype "input"))
      (node (ref "CN3") (pin "3") (pinfunction "3_3") (pintype "input"))
      (node (ref "L2") (pin "2") (pinfunction "2_2") (pintype "input"))
      (node (ref "R43") (pin "1") (pinfunction "1_1") (pintype "input"))
    )
    (net (code "48") (name "Net-(C42-Pad2)") (class "Default")
      (node (ref "C42") (pin "2") (pinfunction "2_2") (pintype "input"))
      (node (ref "L7") (pin "2") (pinfunction "2_2") (pintype "input"))
      (node (ref "U11") (pin "1") (pinfunction "1_1") (pintype "input"))
    )
    (net (code "49") (name "Net-(C43-Pad2)") (class "Default")
      (node (ref "C43") (pin "2") (pinfunction "2_2") (pintype "input"))
      (node (ref "L6") (pin "2") (pinfunction "2_2") (pintype "input"))
      (node (ref "U11") (pin "2") (pinfunction "2_2") (pintype "input"))
    )
    (net (code "50") (name "Net-(C44-Pad2)") (class "Default")
      (node (ref "C44") (pin "2") (pinfunction "2_2") (pintype "input"))
      (node (ref "L9") (pin "2") (pinfunction "2_2") (pintype "input"))
      (node (ref "U10") (pin "1") (pinfunction "1_1") (pintype "input"))
    )
    (net (code "51") (name "Net-(C45-Pad2)") (class "Default")
      (node (ref "C45") (pin "2") (pinfunction "2_2") (pintype "input"))
      (node (ref "L8") (pin "2") (pinfunction "2_2") (pintype "input"))
      (node (ref "U10") (pin "2") (pinfunction "2_2") (pintype "input"))
    )
    (net (code "52") (name "Net-(C49-Pad1)") (class "Default")
      (node (ref "C49") (pin "1") (pinfunction "1_1") (pintype "input"))
      (node (ref "VR1") (pin "2") (pinfunction "2_2") (pintype "input"))
    )
    (net (code "53") (name "Net-(C50-Pad1)") (class "Default")
      (node (ref "C50") (pin "1") (pinfunction "1_1") (pintype "input"))
      (node (ref "VR1") (pin "4") (pinfunction "4_4") (pintype "input"))
    )
    (net (code "54") (name "Net-(DSUB1-Pad1)") (class "Default")
      (node (ref "DSUB1") (pin "1") (pinfunction "1_1") (pintype "input"))
      (node (ref "R14") (pin "2") (pinfunction "2_2") (pintype "input"))
    )
    (net (code "55") (name "Net-(DSUB1-Pad2)") (class "Default")
      (node (ref "DSUB1") (pin "2") (pinfunction "2_2") (pintype "input"))
      (node (ref "R15") (pin "2") (pinfunction "2_2") (pintype "input"))
      (node (ref "R38") (pin "2") (pinfunction "2_2") (pintype "input"))
    )
    (net (code "56") (name "Net-(DSUB1-Pad3)") (class "Default")
      (node (ref "DSUB1") (pin "3") (pinfunction "3_3") (pintype "input"))
      (node (ref "R13") (pin "2") (pinfunction "2_2") (pintype "input"))
    )
    (net (code "57") (name "Net-(LED1-+)") (class "Default")
      (node (ref "LED1") (pin "2") (pinfunction "+_2") (pintype "input"))
      (node (ref "R3") (pin "2") (pinfunction "2_2") (pintype "input"))
    )
    (net (code "58") (name "Net-(R4-Pad2)") (class "Default")
      (node (ref "R4") (pin "2") (pinfunction "2_2") (pintype "input"))
      (node (ref "SW4") (pin "1") (pinfunction "1_1") (pintype "input"))
    )
    (net (code "59") (name "Net-(R33-Pad2)") (class "Default")
      (node (ref "R33") (pin "2") (pinfunction "2_2") (pintype "input"))
      (node (ref "USB2") (pin "1") (pinfunction "EP_1") (pintype "input"))
      (node (ref "USB2") (pin "2") (pinfunction "EP_2") (pintype "input"))
      (node (ref "USB2") (pin "3") (pinfunction "EP_3") (pintype "input"))
      (node (ref "USB2") (pin "4") (pinfunction "EP_4") (pintype "input"))
    )
    (net (code "60") (name "Net-(R42-Pad2)") (class "Default")
      (node (ref "R42") (pin "2") (pinfunction "2_2") (pintype "input"))
      (node (ref "VR1") (pin "5") (pinfunction "5_5") (pintype "input"))
    )
    (net (code "61") (name "Net-(R43-Pad2)") (class "Default")
      (node (ref "R43") (pin "2") (pinfunction "2_2") (pintype "input"))
      (node (ref "VR1") (pin "3") (pinfunction "3_3") (pintype "input"))
    )
    (net (code "62") (name "Net-(U5-QSPI_SCLK)") (class "Default")
      (node (ref "U5") (pin "52") (pinfunction "QSPI_SCLK_52") (pintype "output"))
      (node (ref "U6") (pin "6") (pinfunction "CLK_6") (pintype "input"))
    )
    (net (code "63") (name "Net-(U5-QSPI_SD0)") (class "Default")
      (node (ref "U5") (pin "53") (pinfunction "QSPI_SD0_53") (pintype "bidirectional"))
      (node (ref "U6") (pin "5") (pinfunction "DI_5") (pintype "input"))
    )
    (net (code "64") (name "Net-(U5-QSPI_SD1)") (class "Default")
      (node (ref "U5") (pin "55") (pinfunction "QSPI_SD1_55") (pintype "bidirectional"))
      (node (ref "U6") (pin "2") (pinfunction "DO_2") (pintype "input"))
    )
    (net (code "65") (name "Net-(U5-QSPI_SD2)") (class "Default")
      (node (ref "U5") (pin "54") (pinfunction "QSPI_SD2_54") (pintype "bidirectional"))
      (node (ref "U6") (pin "3") (pinfunction "IO2_3") (pintype "input"))
    )
    (net (code "66") (name "Net-(U5-QSPI_SD3)") (class "Default")
      (node (ref "U5") (pin "51") (pinfunction "QSPI_SD3_51") (pintype "bidirectional"))
      (node (ref "U6") (pin "7") (pinfunction "IO3_7") (pintype "input"))
    )
    (net (code "67") (name "Net-(U5-QSPI_SS)") (class "Default")
      (node (ref "R23") (pin "1") (pinfunction "1_1") (pintype "input"))
      (node (ref "R4") (pin "1") (pinfunction "1_1") (pintype "input"))
      (node (ref "U5") (pin "56") (pinfunction "QSPI_SS_56") (pintype "bidirectional"))
      (node (ref "U6") (pin "1") (pinfunction "CS#_1") (pintype "input"))
    )
    (net (code "68") (name "Net-(U5-USB_DM)") (class "Default")
      (node (ref "R36") (pin "2") (pinfunction "2_2") (pintype "input"))
      (node (ref "U5") (pin "46") (pinfunction "USB_DM_46") (pintype "bidirectional"))
    )
    (net (code "69") (name "Net-(U5-USB_DP)") (class "Default")
      (node (ref "R37") (pin "2") (pinfunction "2_2") (pintype "input"))
      (node (ref "U5") (pin "47") (pinfunction "USB_DP_47") (pintype "bidirectional"))
    )
    (net (code "70") (name "Net-(U5-XIN)") (class "Default")
      (node (ref "C3") (pin "2") (pinfunction "2_2") (pintype "input"))
      (node (ref "U5") (pin "20") (pinfunction "XIN_20") (pintype "input"))
      (node (ref "X1") (pin "3") (pinfunction "OSC2_3") (pintype "input"))
    )
    (net (code "71") (name "Net-(U5-XOUT)") (class "Default")
      (node (ref "R5") (pin "2") (pinfunction "2_2") (pintype "input"))
      (node (ref "U5") (pin "21") (pinfunction "XOUT_21") (pintype "input"))
    )
    (net (code "72") (name "Net-(U8-IN+)") (class "Default")
      (node (ref "C49") (pin "2") (pinfunction "2_2") (pintype "input"))
      (node (ref "U8") (pin "3") (pinfunction "IN+_3") (pintype "input"))
    )
    (net (code "73") (name "Net-(U8-IN-)") (class "Default")
      (node (ref "C48") (pin "2") (pinfunction "2_2") (pintype "input"))
      (node (ref "U8") (pin "4") (pinfunction "IN-_4") (pintype "input"))
    )
    (net (code "74") (name "Net-(U8-SD#)") (class "Default")
      (node (ref "R45") (pin "1") (pinfunction "1_1") (pintype "input"))
      (node (ref "U8") (pin "1") (pinfunction "SD#_1") (pintype "input"))
    )
    (net (code "75") (name "Net-(U8-VO+)") (class "Default")
      (node (ref "L8") (pin "1") (pinfunction "1_1") (pintype "input"))
      (node (ref "U8") (pin "5") (pinfunction "VO+_5") (pintype "output"))
    )
    (net (code "76") (name "Net-(U8-VO-)") (class "Default")
      (node (ref "L9") (pin "1") (pinfunction "1_1") (pintype "input"))
      (node (ref "U8") (pin "8") (pinfunction "VO-_8") (pintype "input"))
    )
    (net (code "77") (name "Net-(U9-IN+)") (class "Default")
      (node (ref "C50") (pin "2") (pinfunction "2_2") (pintype "input"))
      (node (ref "U9") (pin "3") (pinfunction "IN+_3") (pintype "input"))
    )
    (net (code "78") (name "Net-(U9-IN-)") (class "Default")
      (node (ref "C51") (pin "2") (pinfunction "2_2") (pintype "input"))
      (node (ref "U9") (pin "4") (pinfunction "IN-_4") (pintype "input"))
    )
    (net (code "79") (name "Net-(U9-SD#)") (class "Default")
      (node (ref "R44") (pin "1") (pinfunction "1_1") (pintype "input"))
      (node (ref "U9") (pin "1") (pinfunction "SD#_1") (pintype "input"))
    )
    (net (code "80") (name "Net-(U9-VO+)") (class "Default")
      (node (ref "L6") (pin "1") (pinfunction "1_1") (pintype "input"))
      (node (ref "U9") (pin "5") (pinfunction "VO+_5") (pintype "output"))
    )
    (net (code "81") (name "Net-(U9-VO-)") (class "Default")
      (node (ref "L7") (pin "1") (pinfunction "1_1") (pintype "input"))
      (node (ref "U9") (pin "8") (pinfunction "VO-_8") (pintype "input"))
    )
    (net (code "82") (name "Net-(U12A-VBAT)") (class "Default")
      (node (ref "BT4") (pin "1") (pinfunction "1_1") (pintype "input"))
      (node (ref "U12") (pin "14") (pinfunction "VBAT_14") (pintype "unspecified"))
    )
    (net (code "83") (name "Net-(USB2-CC1)") (class "Default")
      (node (ref "R32") (pin "2") (pinfunction "2_2") (pintype "input"))
      (node (ref "USB2") (pin "A5") (pinfunction "CC1_A5") (pintype "input"))
    )
    (net (code "84") (name "Net-(USB2-CC2)") (class "Default")
      (node (ref "R31") (pin "2") (pinfunction "2_2") (pintype "input"))
      (node (ref "USB2") (pin "B5") (pinfunction "CC2_B5") (pintype "input"))
    )
    (net (code "85") (name "Net-(USB5-D+)") (class "Default")
      (node (ref "R37") (pin "1") (pinfunction "1_1") (pintype "input"))
      (node (ref "R47") (pin "1") (pinfunction "1_1") (pintype "input"))
      (node (ref "USB5") (pin "3") (pinfunction "D+_3") (pintype "unspecified"))
    )
    (net (code "86") (name "Net-(USB5-D-)") (class "Default")
      (node (ref "R36") (pin "1") (pinfunction "1_1") (pintype "input"))
      (node (ref "R46") (pin "1") (pinfunction "1_1") (pintype "input"))
      (node (ref "USB5") (pin "2") (pinfunction "D-_2") (pintype "unspecified"))
    )
    (net (code "87") (name "Net-(X1-OSC1)") (class "Default")
      (node (ref "C4") (pin "2") (pinfunction "2_2") (pintype "input"))
      (node (ref "R5") (pin "1") (pinfunction "1_1") (pintype "input"))
      (node (ref "X1") (pin "1") (pinfunction "OSC1_1") (pintype "input"))
    )
    (net (code "88") (name "VCC") (class "Default")
      (node (ref "C10") (pin "2") (pinfunction "2_2") (pintype "input"))
      (node (ref "C11") (pin "2") (pinfunction "2_2") (pintype "input"))
      (node (ref "C12") (pin "2") (pinfunction "2_2") (pintype "input"))
      (node (ref "C18") (pin "2") (pinfunction "2_2") (pintype "input"))
      (node (ref "C20") (pin "2") (pinfunction "2_2") (pintype "input"))
      (node (ref "C22") (pin "2") (pinfunction "2_2") (pintype "input"))
      (node (ref "C26") (pin "2") (pinfunction "2_2") (pintype "input"))
      (node (ref "C34") (pin "1") (pinfunction "1_1") (pintype "input"))
      (node (ref "C5") (pin "2") (pinfunction "2_2") (pintype "input"))
      (node (ref "C6") (pin "2") (pinfunction "2_2") (pintype "input"))
      (node (ref "C7") (pin "2") (pinfunction "2_2") (pintype "input"))
      (node (ref "C8") (pin "2") (pinfunction "2_2") (pintype "input"))
      (node (ref "C9") (pin "2") (pinfunction "2_2") (pintype "input"))
      (node (ref "CN2") (pin "10") (pinfunction "10_10") (pintype "input"))
      (node (ref "CN2") (pin "12") (pinfunction "12_12") (pintype "input"))
      (node (ref "L3") (pin "2") (pinfunction "2_2") (pintype "input"))
      (node (ref "R11") (pin "2") (pinfunction "2_2") (pintype "input"))
      (node (ref "R12") (pin "2") (pinfunction "2_2") (pintype "input"))
      (node (ref "R23") (pin "2") (pinfunction "2_2") (pintype "input"))
      (node (ref "R28") (pin "2") (pinfunction "2_2") (pintype "input"))
      (node (ref "R29") (pin "1") (pinfunction "1_1") (pintype "input"))
      (node (ref "U1") (pin "2") (pinfunction "VOUT_2") (pintype "input"))
      (node (ref "U1") (pin "4") (pinfunction "VOUT_4") (pintype "input"))
      (node (ref "U12") (pin "2") (pinfunction "VCC_2") (pintype "unspecified"))
      (node (ref "U12") (pin "4") (pinfunction "RST_4") (pintype "bidirectional"))
      (node (ref "U5") (pin "1") (pinfunction "IOVDD_1") (pintype "bidirectional"))
      (node (ref "U5") (pin "10") (pinfunction "IOVDD_10") (pintype "bidirectional"))
      (node (ref "U5") (pin "22") (pinfunction "IOVDD_22") (pintype "bidirectional"))
      (node (ref "U5") (pin "33") (pinfunction "IOVDD_33") (pintype "bidirectional"))
      (node (ref "U5") (pin "42") (pinfunction "IOVDD_42") (pintype "bidirectional"))
      (node (ref "U5") (pin "44") (pinfunction "VREG_IN_44") (pintype "bidirectional"))
      (node (ref "U5") (pin "48") (pinfunction "USB_VDD_48") (pintype "bidirectional"))
      (node (ref "U5") (pin "49") (pinfunction "IOVDD_49") (pintype "bidirectional"))
      (node (ref "U6") (pin "8") (pinfunction "VCC_8") (pintype "input"))
      (node (ref "U7") (pin "16") (pinfunction "VCC_16") (pintype "input"))
      (node (ref "U7") (pin "4") (pinfunction "V3_4") (pintype "input"))
    )
    (net (code "89") (name "unconnected-(CARD2-DAT1-Pad8)") (class "Default")
      (node (ref "CARD2") (pin "8") (pinfunction "DAT1_8") (pintype "input+no_connect"))
    )
    (net (code "90") (name "unconnected-(CARD2-DAT2-Pad1)") (class "Default")
      (node (ref "CARD2") (pin "1") (pinfunction "DAT2_1") (pintype "input+no_connect"))
    )
    (net (code "91") (name "unconnected-(CARD2-PadCD)") (class "Default")
      (node (ref "CARD2") (pin "CD") (pinfunction "CD_CD") (pintype "input+no_connect"))
    )
    (net (code "92") (name "unconnected-(DSUB1-Pad4)") (class "Default")
      (node (ref "DSUB1") (pin "4") (pinfunction "4_4") (pintype "input+no_connect"))
    )
    (net (code "93") (name "unconnected-(DSUB1-Pad9)") (class "Default")
      (node (ref "DSUB1") (pin "9") (pinfunction "9_9") (pintype "input+no_connect"))
    )
    (net (code "94") (name "unconnected-(DSUB1-Pad11)") (class "Default")
      (node (ref "DSUB1") (pin "11") (pinfunction "11_11") (pintype "input+no_connect"))
    )
    (net (code "95") (name "unconnected-(DSUB1-Pad12)") (class "Default")
      (node (ref "DSUB1") (pin "12") (pinfunction "12_12") (pintype "input+no_connect"))
    )
    (net (code "96") (name "unconnected-(DSUB1-Pad15)") (class "Default")
      (node (ref "DSUB1") (pin "15") (pinfunction "15_15") (pintype "input+no_connect"))
    )
    (net (code "97") (name "unconnected-(U5-SWCLK-Pad24)") (class "Default")
      (node (ref "U5") (pin "24") (pinfunction "SWCLK_24") (pintype "output+no_connect"))
    )
    (net (code "98") (name "unconnected-(U5-SWD-Pad25)") (class "Default")
      (node (ref "U5") (pin "25") (pinfunction "SWD_25") (pintype "bidirectional+no_connect"))
    )
    (net (code "99") (name "unconnected-(U7-CTS#-Pad9)") (class "Default")
      (node (ref "U7") (pin "9") (pinfunction "CTS#_9") (pintype "input+no_connect"))
    )
    (net (code "100") (name "unconnected-(U7-DCD#-Pad12)") (class "Default")
      (node (ref "U7") (pin "12") (pinfunction "DCD#_12") (pintype "input+no_connect"))
    )
    (net (code "101") (name "unconnected-(U7-DSR#-Pad10)") (class "Default")
      (node (ref "U7") (pin "10") (pinfunction "DSR#_10") (pintype "input+no_connect"))
    )
    (net (code "102") (name "unconnected-(U7-DTR#-Pad13)") (class "Default")
      (node (ref "U7") (pin "13") (pinfunction "DTR#_13") (pintype "input+no_connect"))
    )
    (net (code "103") (name "unconnected-(U7-NC.-Pad7)") (class "Default")
      (node (ref "U7") (pin "7") (pinfunction "NC._7") (pintype "input+no_connect"))
    )
    (net (code "104") (name "unconnected-(U7-OUT#-Pad8)") (class "Default")
      (node (ref "U7") (pin "8") (pinfunction "OUT#_8") (pintype "input+no_connect"))
    )
    (net (code "105") (name "unconnected-(U7-R232-Pad15)") (class "Default")
      (node (ref "U7") (pin "15") (pinfunction "R232_15") (pintype "input+no_connect"))
    )
    (net (code "106") (name "unconnected-(U7-RI#-Pad11)") (class "Default")
      (node (ref "U7") (pin "11") (pinfunction "RI#_11") (pintype "input+no_connect"))
    )
    (net (code "107") (name "unconnected-(U7-RTS#-Pad14)") (class "Default")
      (node (ref "U7") (pin "14") (pinfunction "RTS#_14") (pintype "input+no_connect"))
    )
    (net (code "108") (name "unconnected-(U8-NC-Pad2)") (class "Default")
      (node (ref "U8") (pin "2") (pinfunction "NC_2") (pintype "input+no_connect"))
    )
    (net (code "109") (name "unconnected-(U9-NC-Pad2)") (class "Default")
      (node (ref "U9") (pin "2") (pinfunction "NC_2") (pintype "input+no_connect"))
    )
    (net (code "110") (name "unconnected-(U12A-32kHz-Pad1)") (class "Default")
      (node (ref "U12") (pin "1") (pinfunction "32kHz_1") (pintype "unspecified+no_connect"))
    )
    (net (code "111") (name "unconnected-(U12A-INTSQW-Pad3)") (class "Default")
      (node (ref "U12") (pin "3") (pinfunction "INTSQW_3") (pintype "unspecified+no_connect"))
    )
    (net (code "112") (name "unconnected-(USB2-SUB1-PadA8)") (class "Default")
      (node (ref "USB2") (pin "A8") (pinfunction "SUB1_A8") (pintype "input+no_connect"))
    )
    (net (code "113") (name "unconnected-(USB2-SUB2-PadB8)") (class "Default")
      (node (ref "USB2") (pin "B8") (pinfunction "SUB2_B8") (pintype "input+no_connect"))
    )
  )
)
